# Schematix.net
KiCad netlist of a schematic drawn in EAGLE
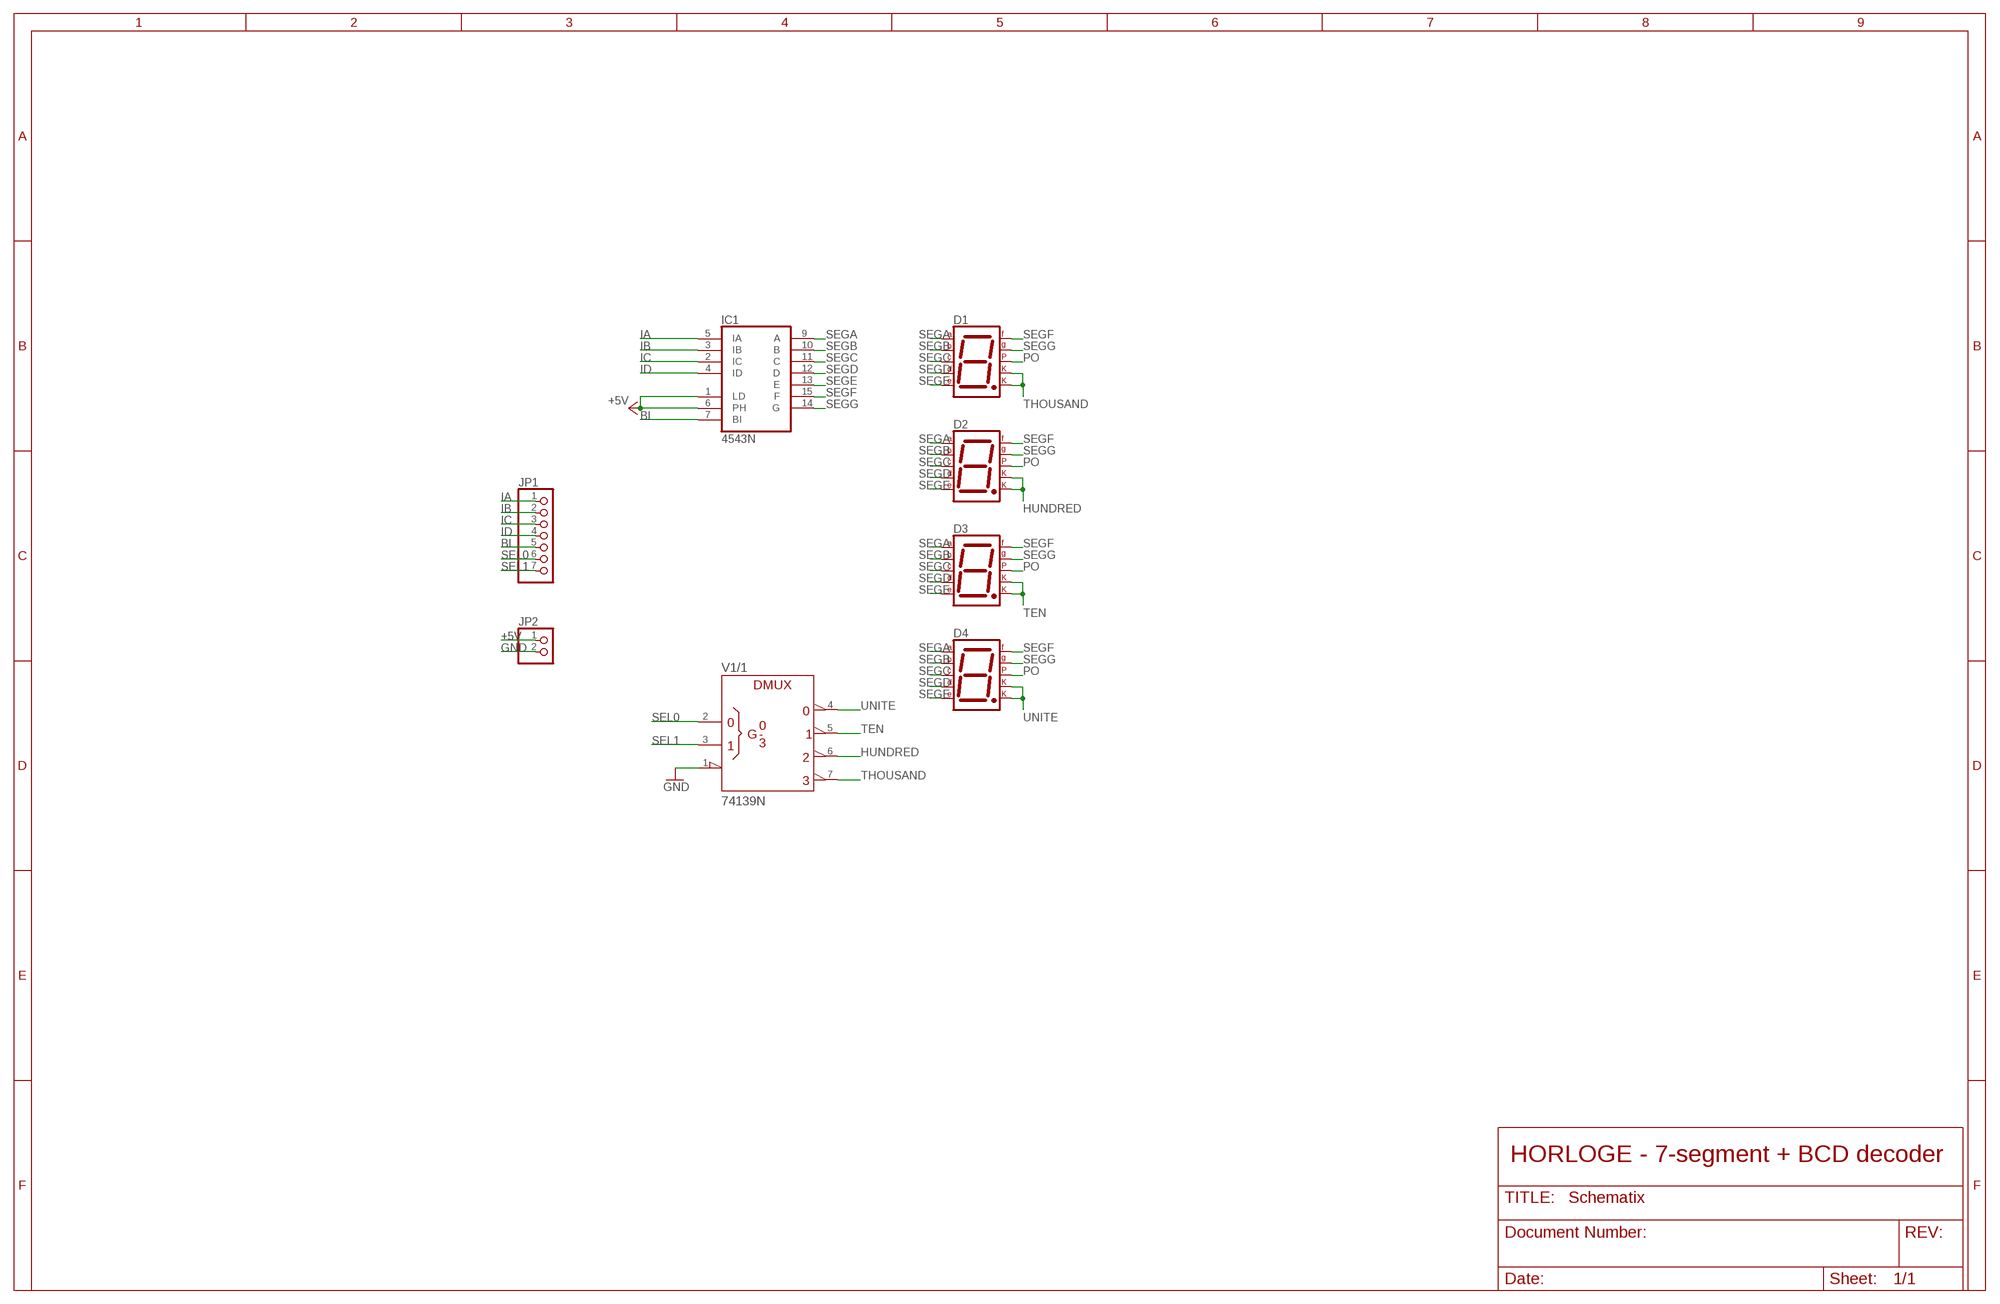
[diagram p0: schematic, sheet 1]

(export (version "E")
  (design (tool "Eeschema 10.0.6"))
  (components
    (comp (ref "D1")
      (value "7SEG-CK")
      (footprint "eagle-import:7SEG-13")
      (libsource (lib "eagle-import") (part "7SEG-CK"))
    )
    (comp (ref "D2")
      (value "7SEG-CK")
      (footprint "eagle-import:7SEG-13")
      (libsource (lib "eagle-import") (part "7SEG-CK"))
    )
    (comp (ref "D3")
      (value "7SEG-CK")
      (footprint "eagle-import:7SEG-13")
      (libsource (lib "eagle-import") (part "7SEG-CK"))
    )
    (comp (ref "D4")
      (value "7SEG-CK")
      (footprint "eagle-import:7SEG-13")
      (libsource (lib "eagle-import") (part "7SEG-CK"))
    )
    (comp (ref "IC1")
      (value "4543N")
      (footprint "eagle-import:DIL16")
      (libsource (lib "eagle-import") (part "4543N"))
    )
    (comp (ref "JP1")
      (value "PINHD-1X7/90")
      (footprint "eagle-import:1X07_90")
      (libsource (lib "eagle-import") (part "PINHD-1X7/90"))
    )
    (comp (ref "JP2")
      (value "PINHD-1X2/90")
      (footprint "eagle-import:1X02_90")
      (libsource (lib "eagle-import") (part "PINHD-1X2/90"))
    )
    (comp (ref "V1")
      (value "74139N")
      (footprint "eagle-import:DIL16")
      (libsource (lib "eagle-import") (part "74139N"))
    )
  )
  (nets
    (net (code "1") (name "+5V") (class "Default")
      (node (ref "IC1") (pin "1") (pinfunction "LD_1") (pintype "input"))
      (node (ref "IC1") (pin "6") (pinfunction "PH_6") (pintype "input"))
      (node (ref "JP2") (pin "1") (pinfunction "1_1") (pintype "passive"))
    )
    (net (code "2") (name "/BI") (class "Default")
      (node (ref "IC1") (pin "7") (pinfunction "BI_7") (pintype "input"))
      (node (ref "JP1") (pin "5") (pinfunction "5_5") (pintype "passive"))
    )
    (net (code "3") (name "/HUNDRED") (class "Default")
      (node (ref "D2") (pin "3") (pinfunction "CK1_3") (pintype "passive"))
      (node (ref "D2") (pin "8") (pinfunction "CK2_8") (pintype "passive"))
      (node (ref "V1") (pin "6") (pinfunction "Y2_6") (pintype "output"))
    )
    (net (code "4") (name "/IA") (class "Default")
      (node (ref "IC1") (pin "5") (pinfunction "IA_5") (pintype "input"))
      (node (ref "JP1") (pin "1") (pinfunction "1_1") (pintype "passive"))
    )
    (net (code "5") (name "/IB") (class "Default")
      (node (ref "IC1") (pin "3") (pinfunction "IB_3") (pintype "input"))
      (node (ref "JP1") (pin "2") (pinfunction "2_2") (pintype "passive"))
    )
    (net (code "6") (name "/IC") (class "Default")
      (node (ref "IC1") (pin "2") (pinfunction "IC_2") (pintype "input"))
      (node (ref "JP1") (pin "3") (pinfunction "3_3") (pintype "passive"))
    )
    (net (code "7") (name "/ID") (class "Default")
      (node (ref "IC1") (pin "4") (pinfunction "ID_4") (pintype "input"))
      (node (ref "JP1") (pin "4") (pinfunction "4_4") (pintype "passive"))
    )
    (net (code "8") (name "/PO") (class "Default")
      (node (ref "D1") (pin "5") (pinfunction "DP_5") (pintype "passive"))
      (node (ref "D2") (pin "5") (pinfunction "DP_5") (pintype "passive"))
      (node (ref "D3") (pin "5") (pinfunction "DP_5") (pintype "passive"))
      (node (ref "D4") (pin "5") (pinfunction "DP_5") (pintype "passive"))
    )
    (net (code "9") (name "/SEGA") (class "Default")
      (node (ref "D1") (pin "7") (pinfunction "A_7") (pintype "passive"))
      (node (ref "D2") (pin "7") (pinfunction "A_7") (pintype "passive"))
      (node (ref "D3") (pin "7") (pinfunction "A_7") (pintype "passive"))
      (node (ref "D4") (pin "7") (pinfunction "A_7") (pintype "passive"))
      (node (ref "IC1") (pin "9") (pinfunction "A_9") (pintype "output"))
    )
    (net (code "10") (name "/SEGB") (class "Default")
      (node (ref "D1") (pin "6") (pinfunction "B_6") (pintype "passive"))
      (node (ref "D2") (pin "6") (pinfunction "B_6") (pintype "passive"))
      (node (ref "D3") (pin "6") (pinfunction "B_6") (pintype "passive"))
      (node (ref "D4") (pin "6") (pinfunction "B_6") (pintype "passive"))
      (node (ref "IC1") (pin "10") (pinfunction "B_10") (pintype "output"))
    )
    (net (code "11") (name "/SEGC") (class "Default")
      (node (ref "D1") (pin "4") (pinfunction "C_4") (pintype "passive"))
      (node (ref "D2") (pin "4") (pinfunction "C_4") (pintype "passive"))
      (node (ref "D3") (pin "4") (pinfunction "C_4") (pintype "passive"))
      (node (ref "D4") (pin "4") (pinfunction "C_4") (pintype "passive"))
      (node (ref "IC1") (pin "11") (pinfunction "C_11") (pintype "output"))
    )
    (net (code "12") (name "/SEGD") (class "Default")
      (node (ref "D1") (pin "2") (pinfunction "D_2") (pintype "passive"))
      (node (ref "D2") (pin "2") (pinfunction "D_2") (pintype "passive"))
      (node (ref "D3") (pin "2") (pinfunction "D_2") (pintype "passive"))
      (node (ref "D4") (pin "2") (pinfunction "D_2") (pintype "passive"))
      (node (ref "IC1") (pin "12") (pinfunction "D_12") (pintype "output"))
    )
    (net (code "13") (name "/SEGE") (class "Default")
      (node (ref "D1") (pin "1") (pinfunction "E_1") (pintype "passive"))
      (node (ref "D2") (pin "1") (pinfunction "E_1") (pintype "passive"))
      (node (ref "D3") (pin "1") (pinfunction "E_1") (pintype "passive"))
      (node (ref "D4") (pin "1") (pinfunction "E_1") (pintype "passive"))
      (node (ref "IC1") (pin "13") (pinfunction "E_13") (pintype "output"))
    )
    (net (code "14") (name "/SEGF") (class "Default")
      (node (ref "D1") (pin "9") (pinfunction "F_9") (pintype "passive"))
      (node (ref "D2") (pin "9") (pinfunction "F_9") (pintype "passive"))
      (node (ref "D3") (pin "9") (pinfunction "F_9") (pintype "passive"))
      (node (ref "D4") (pin "9") (pinfunction "F_9") (pintype "passive"))
      (node (ref "IC1") (pin "15") (pinfunction "F_15") (pintype "output"))
    )
    (net (code "15") (name "/SEGG") (class "Default")
      (node (ref "D1") (pin "10") (pinfunction "G_10") (pintype "passive"))
      (node (ref "D2") (pin "10") (pinfunction "G_10") (pintype "passive"))
      (node (ref "D3") (pin "10") (pinfunction "G_10") (pintype "passive"))
      (node (ref "D4") (pin "10") (pinfunction "G_10") (pintype "passive"))
      (node (ref "IC1") (pin "14") (pinfunction "G_14") (pintype "output"))
    )
    (net (code "16") (name "/SEL0") (class "Default")
      (node (ref "JP1") (pin "6") (pinfunction "6_6") (pintype "passive"))
      (node (ref "V1") (pin "2") (pinfunction "A_2") (pintype "input"))
    )
    (net (code "17") (name "/SEL1") (class "Default")
      (node (ref "JP1") (pin "7") (pinfunction "7_7") (pintype "passive"))
      (node (ref "V1") (pin "3") (pinfunction "B_3") (pintype "input"))
    )
    (net (code "18") (name "/TEN") (class "Default")
      (node (ref "D3") (pin "3") (pinfunction "CK1_3") (pintype "passive"))
      (node (ref "D3") (pin "8") (pinfunction "CK2_8") (pintype "passive"))
      (node (ref "V1") (pin "5") (pinfunction "Y1_5") (pintype "output"))
    )
    (net (code "19") (name "/THOUSAND") (class "Default")
      (node (ref "D1") (pin "3") (pinfunction "CK1_3") (pintype "passive"))
      (node (ref "D1") (pin "8") (pinfunction "CK2_8") (pintype "passive"))
      (node (ref "V1") (pin "7") (pinfunction "Y3_7") (pintype "output"))
    )
    (net (code "20") (name "/UNITE") (class "Default")
      (node (ref "D4") (pin "3") (pinfunction "CK1_3") (pintype "passive"))
      (node (ref "D4") (pin "8") (pinfunction "CK2_8") (pintype "passive"))
      (node (ref "V1") (pin "4") (pinfunction "Y0_4") (pintype "output"))
    )
    (net (code "21") (name "GND") (class "Default")
      (node (ref "JP2") (pin "2") (pinfunction "2_2") (pintype "passive"))
      (node (ref "V1") (pin "1") (pinfunction "~{G}_1") (pintype "input"))
    )
  )
)
